# stm32.net
KiCad netlist of a schematic drawn in Altium Designer
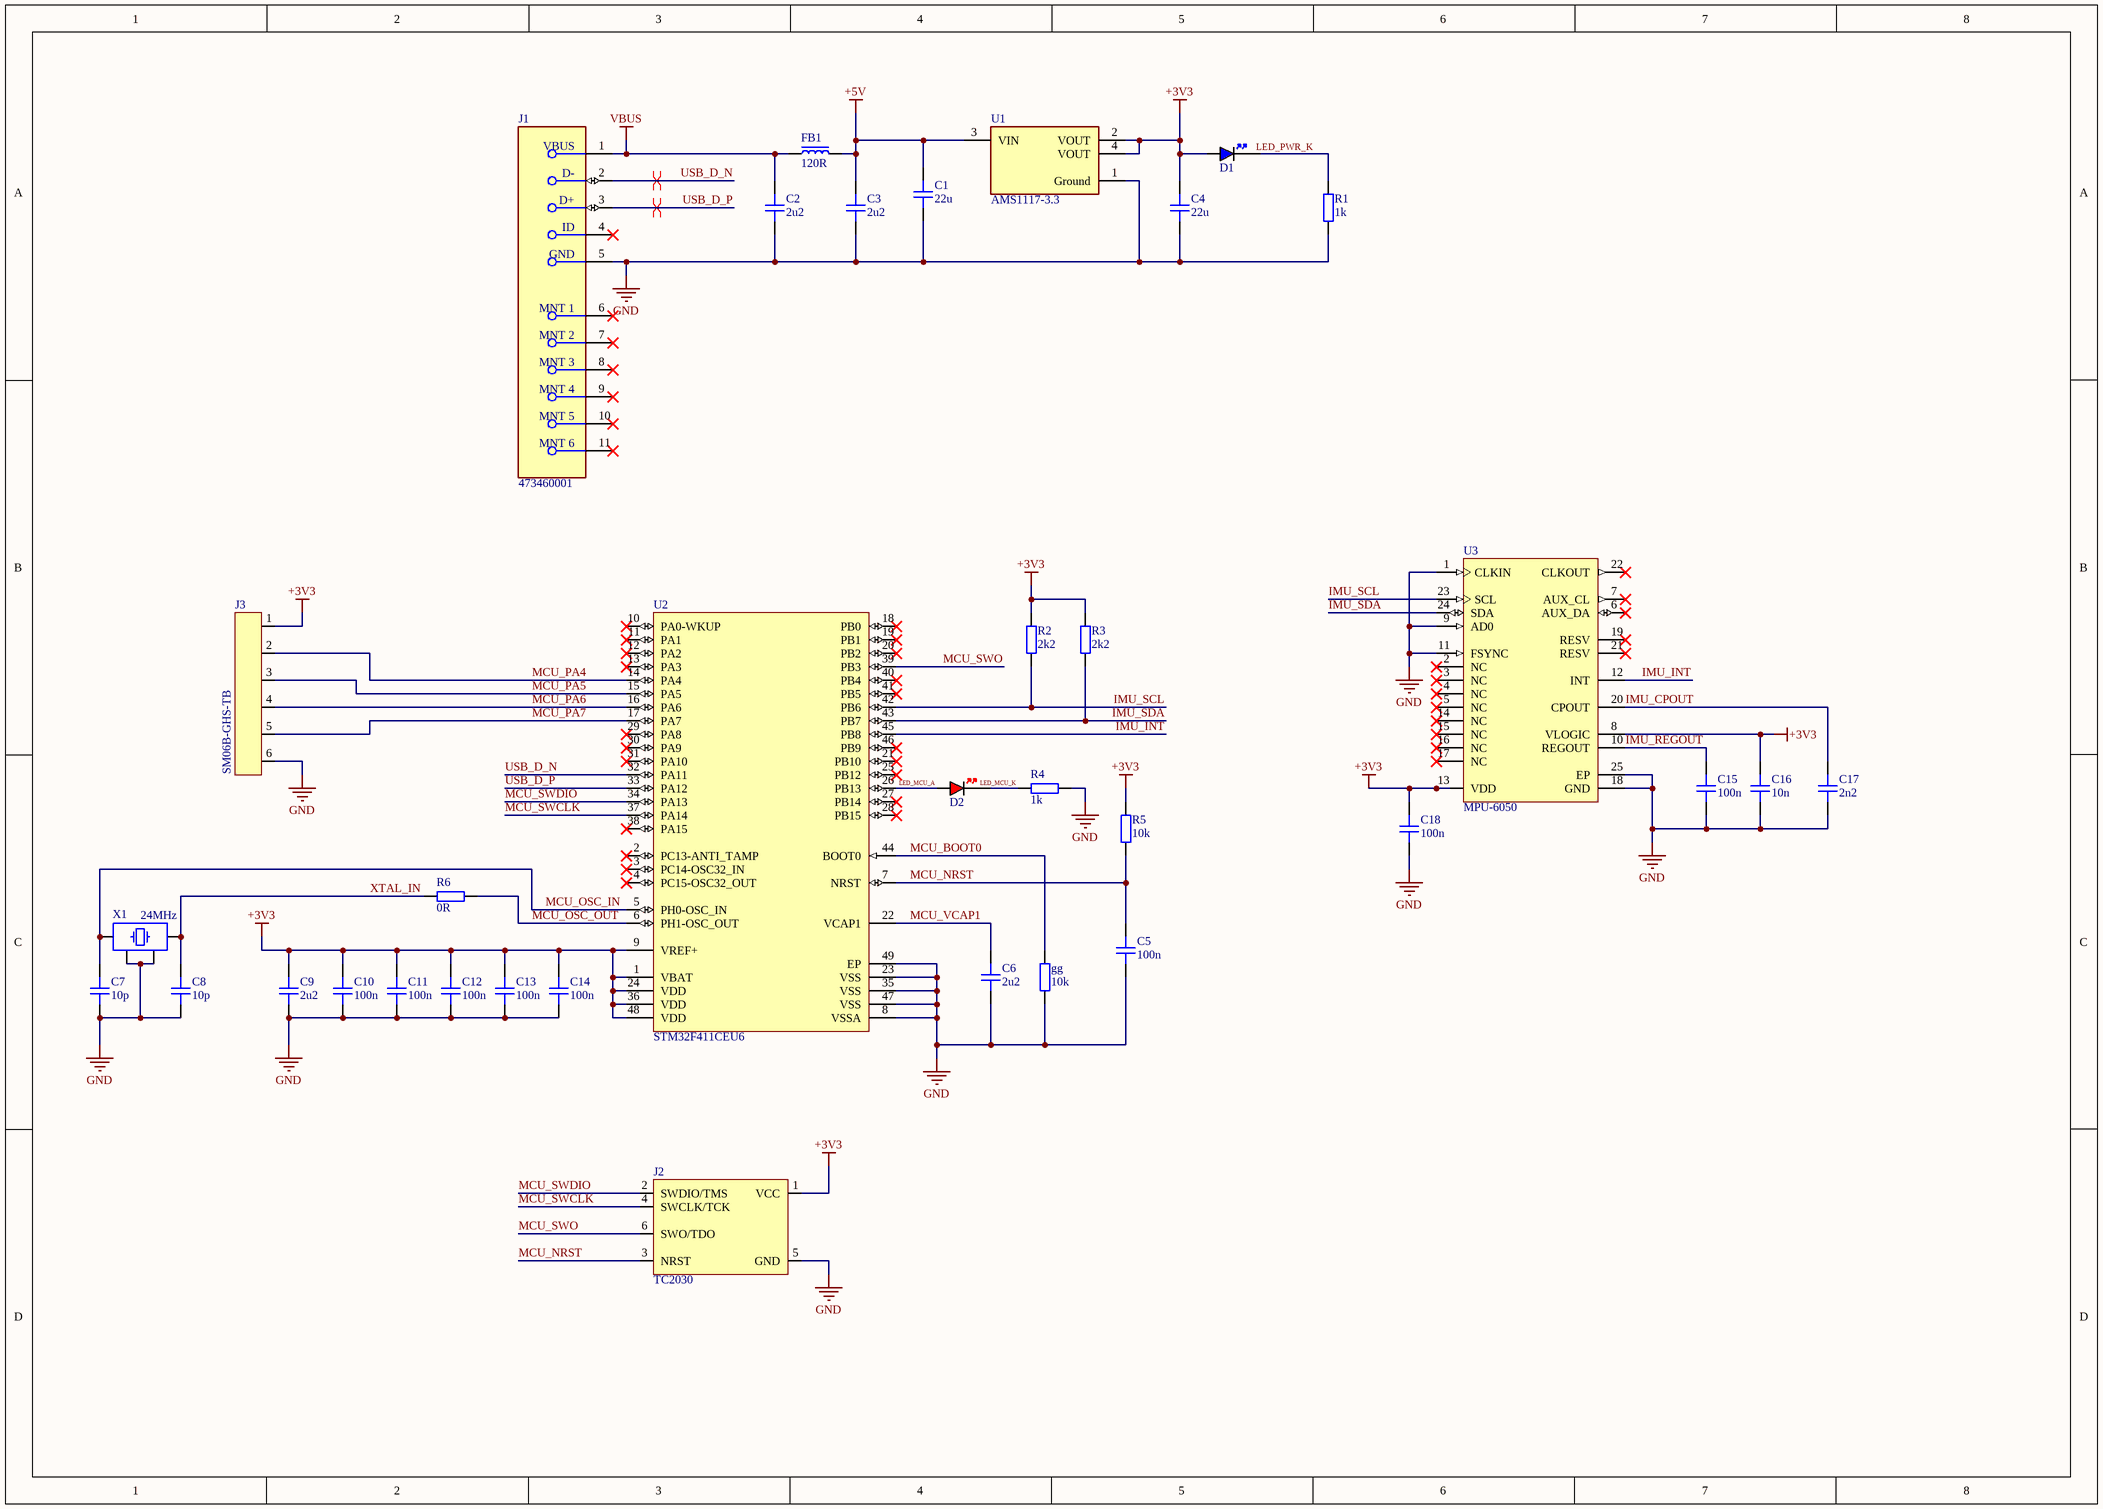
[diagram p0: stm32.SchDoc]

(export (version "E")
  (design (tool "Eeschema 10.0.6"))
  (components
    (comp (ref "C1")
      (value "22u")
      (footprint "CAP_0805")
      (description "Capacitor SMD 0805")
      (libsource (lib "Schematic-Lib-PhilsLab") (part "CAP_0805"))
    )
    (comp (ref "C2")
      (value "2u2")
      (footprint "CAP_0603")
      (description "Capacitor SMD 0603")
      (libsource (lib "Schematic-Lib-PhilsLab") (part "CAP_0603"))
    )
    (comp (ref "C3")
      (value "2u2")
      (footprint "CAP_0603")
      (description "Capacitor SMD 0603")
      (libsource (lib "Schematic-Lib-PhilsLab") (part "CAP_0603"))
    )
    (comp (ref "C4")
      (value "22u")
      (footprint "CAP_0805")
      (description "Capacitor SMD 0805")
      (libsource (lib "Schematic-Lib-PhilsLab") (part "CAP_0805"))
    )
    (comp (ref "C5")
      (value "100n")
      (footprint "CAP_0402")
      (description "Capacitor SMD 0402")
      (libsource (lib "Schematic-Lib-PhilsLab") (part "CAP_0402"))
    )
    (comp (ref "C6")
      (value "2u2")
      (footprint "CAP_0603")
      (description "Capacitor SMD 0603")
      (libsource (lib "Schematic-Lib-PhilsLab") (part "CAP_0603"))
    )
    (comp (ref "C7")
      (value "10p")
      (footprint "CAP_0402")
      (description "Capacitor SMD 0402")
      (libsource (lib "Schematic-Lib-PhilsLab") (part "CAP_0402"))
    )
    (comp (ref "C8")
      (value "10p")
      (footprint "CAP_0402")
      (description "Capacitor SMD 0402")
      (libsource (lib "Schematic-Lib-PhilsLab") (part "CAP_0402"))
    )
    (comp (ref "C9")
      (value "2u2")
      (footprint "CAP_0603")
      (description "Capacitor SMD 0603")
      (libsource (lib "Schematic-Lib-PhilsLab") (part "CAP_0603"))
    )
    (comp (ref "C10")
      (value "100n")
      (footprint "CAP_0402")
      (description "Capacitor SMD 0402")
      (libsource (lib "Schematic-Lib-PhilsLab") (part "CAP_0402"))
    )
    (comp (ref "C11")
      (value "100n")
      (footprint "CAP_0402")
      (description "Capacitor SMD 0402")
      (libsource (lib "Schematic-Lib-PhilsLab") (part "CAP_0402"))
    )
    (comp (ref "C12")
      (value "100n")
      (footprint "CAP_0402")
      (description "Capacitor SMD 0402")
      (libsource (lib "Schematic-Lib-PhilsLab") (part "CAP_0402"))
    )
    (comp (ref "C13")
      (value "100n")
      (footprint "CAP_0402")
      (description "Capacitor SMD 0402")
      (libsource (lib "Schematic-Lib-PhilsLab") (part "CAP_0402"))
    )
    (comp (ref "C14")
      (value "100n")
      (footprint "CAP_0402")
      (description "Capacitor SMD 0402")
      (libsource (lib "Schematic-Lib-PhilsLab") (part "CAP_0402"))
    )
    (comp (ref "C15")
      (value "100n")
      (footprint "CAP_0402")
      (description "Capacitor SMD 0402")
      (libsource (lib "Schematic-Lib-PhilsLab") (part "CAP_0402"))
    )
    (comp (ref "C16")
      (value "10n")
      (footprint "CAP_0402")
      (description "Capacitor SMD 0402")
      (libsource (lib "Schematic-Lib-PhilsLab") (part "CAP_0402"))
    )
    (comp (ref "C17")
      (value "2n2")
      (footprint "CAP_0402")
      (description "Capacitor SMD 0402")
      (libsource (lib "Schematic-Lib-PhilsLab") (part "CAP_0402"))
    )
    (comp (ref "C18")
      (value "100n")
      (footprint "CAP_0402")
      (description "Capacitor SMD 0402")
      (libsource (lib "Schematic-Lib-PhilsLab") (part "CAP_0402"))
    )
    (comp (ref "D1")
      (value "BLUE")
      (footprint "LED_0402_BLUE")
      (description "LED 0402 BLUE SMD")
      (libsource (lib "Schematic-Lib-PhilsLab") (part "LED_0402_BLUE"))
    )
    (comp (ref "D2")
      (value "RED")
      (footprint "LED_0402_RED")
      (description "LED 0402 RED SMD")
      (libsource (lib "Schematic-Lib-PhilsLab") (part "LED_0402_RED"))
    )
    (comp (ref "FB1")
      (value "120R")
      (footprint "FB_0603")
      (description "Ferrite Bead SMD 0603")
      (libsource (lib "Schematic-Lib-PhilsLab") (part "FB_0603"))
    )
    (comp (ref "gg")
      (value "10k")
      (footprint "RES_0402")
      (description "Resistor SMD 0402")
      (libsource (lib "Schematic-Lib-PhilsLab") (part "RES_0402"))
    )
    (comp (ref "J1")
      (value "473460001")
      (footprint "FP-473460001-MFG")
      (description "CONN RCPT USB2.0 MICRO B SMD R/A")
      (fields
        (field (name "OCTOPART") "https://octopart.com/47346-0001-molex-7164928")
        (field (name "MANUFACTURER") "Molex")
      )
      (libsource (lib "Altium Content Vault") (part "53ae1f1d9b557310b43ca686e5bb76a"))
    )
    (comp (ref "J2")
      (value "TC2030")
      (footprint "TC2030-FP")
      (description "Tag-Connect No-Solder SWD Debug Connector DO NOT PLACE")
      (fields (field (name "MANUFACTURER") "Tag-Connect"))
      (libsource (lib "Schematic-Lib-PhilsLab") (part "TC2030"))
    )
    (comp (ref "J3")
      (value "SM06B-GHS-TB")
      (footprint "SM06B-GHS-TB")
      (description "Header Connector 6 Position 1.25MM Pitch SMD Horizontal JST GH")
      (fields (field (name "MANUFACTURER") "JST"))
      (libsource (lib "Schematic-Lib-PhilsLab") (part "SM06B-GHS-TB"))
    )
    (comp (ref "R1")
      (value "1k")
      (footprint "RES_0402")
      (description "Resistor SMD 0402")
      (libsource (lib "Schematic-Lib-PhilsLab") (part "RES_0402"))
    )
    (comp (ref "R2")
      (value "2k2")
      (footprint "RES_0402")
      (description "Resistor SMD 0402")
      (libsource (lib "Schematic-Lib-PhilsLab") (part "RES_0402"))
    )
    (comp (ref "R3")
      (value "2k2")
      (footprint "RES_0402")
      (description "Resistor SMD 0402")
      (libsource (lib "Schematic-Lib-PhilsLab") (part "RES_0402"))
    )
    (comp (ref "R4")
      (value "1k")
      (footprint "RES_0402")
      (description "Resistor SMD 0402")
      (libsource (lib "Schematic-Lib-PhilsLab") (part "RES_0402"))
    )
    (comp (ref "R5")
      (value "10k")
      (footprint "RES_0402")
      (description "Resistor SMD 0402")
      (libsource (lib "Schematic-Lib-PhilsLab") (part "RES_0402"))
    )
    (comp (ref "R6")
      (value "0R")
      (footprint "RES_0402")
      (description "Resistor SMD 0402")
      (libsource (lib "Schematic-Lib-PhilsLab") (part "RES_0402"))
    )
    (comp (ref "U1")
      (value "AMS1117-3.3")
      (footprint "FP-AMS1117-IPC_C")
      (description "LDO Voltage Regulators 1A, 3.3V")
      (fields
        (field (name "OCTOPART") "https://octopart.com/ams1117-3.3-advanced+monolithic+systems-25899300")
        (field (name "MANUFACTURER") "Advanced Monolithic Systems")
      )
      (libsource (lib "Altium Content Vault") (part "8bdbb5f8e77002000e30dd2845d0354"))
    )
    (comp (ref "U2")
      (value "STM32F411CEU6")
      (footprint "STM-UFQFPN48_L")
      (libsource (lib "Altium Content Vault") (part "MC-ARM-STM32F411-UFQFPN48"))
    )
    (comp (ref "U3")
      (value "MPU-6050")
      (footprint "IS-QFN-24_V")
      (fields (field (name "MANUFACTURER") "InvenSense"))
      (libsource (lib "Altium Content Vault") (part "IS-MPU-6050-QFN-24"))
    )
    (comp (ref "X1")
      (value "24MHz")
      (footprint "XTAL_3225")
      (description "Crystal SMD 24MHz 10PPM 7pF 3225")
      (fields
        (field (name "MANUFACTURER") "Epson")
        (field (name "MANUFACTURER PART NUMBER") "TSX-3225 24.0000MF15X-AC")
      )
      (libsource (lib "Schematic-Lib-PhilsLab") (part "TSX-3225_24.0000MF15X-AC"))
    )
  )
  (nets
    (net (code "1") (name "+3V3") (class "Default")
      (node (ref "C10") (pin "2") (pinfunction "2_2") (pintype "passive"))
      (node (ref "C11") (pin "2") (pinfunction "2_2") (pintype "passive"))
      (node (ref "C12") (pin "2") (pinfunction "2_2") (pintype "passive"))
      (node (ref "C13") (pin "2") (pinfunction "2_2") (pintype "passive"))
      (node (ref "C14") (pin "2") (pinfunction "2_2") (pintype "passive"))
      (node (ref "C16") (pin "2") (pinfunction "2_2") (pintype "passive"))
      (node (ref "C18") (pin "2") (pinfunction "2_2") (pintype "passive"))
      (node (ref "C4") (pin "2") (pinfunction "2_2") (pintype "passive"))
      (node (ref "C9") (pin "2") (pinfunction "2_2") (pintype "passive"))
      (node (ref "D1") (pin "A") (pinfunction "A_A") (pintype "passive"))
      (node (ref "J2") (pin "1") (pinfunction "VCC_1") (pintype "passive"))
      (node (ref "J3") (pin "1") (pinfunction "1_1") (pintype "passive"))
      (node (ref "R2") (pin "2") (pinfunction "2_2") (pintype "passive"))
      (node (ref "R3") (pin "2") (pinfunction "2_2") (pintype "passive"))
      (node (ref "R5") (pin "2") (pinfunction "2_2") (pintype "passive"))
      (node (ref "U1") (pin "2") (pinfunction "VOUT_2") (pintype "passive"))
      (node (ref "U1") (pin "4") (pinfunction "VOUT_4") (pintype "passive"))
      (node (ref "U2") (pin "1") (pinfunction "VBAT_1") (pintype "power_in"))
      (node (ref "U2") (pin "24") (pinfunction "VDD_24") (pintype "power_in"))
      (node (ref "U2") (pin "36") (pinfunction "VDD_36") (pintype "power_in"))
      (node (ref "U2") (pin "48") (pinfunction "VDD_48") (pintype "power_in"))
      (node (ref "U2") (pin "9") (pinfunction "VREF+_9") (pintype "power_in"))
      (node (ref "U3") (pin "13") (pinfunction "VDD_13") (pintype "power_in"))
      (node (ref "U3") (pin "8") (pinfunction "VLOGIC_8") (pintype "power_in"))
    )
    (net (code "2") (name "+5V") (class "Default")
      (node (ref "C1") (pin "2") (pinfunction "2_2") (pintype "passive"))
      (node (ref "C3") (pin "2") (pinfunction "2_2") (pintype "passive"))
      (node (ref "FB1") (pin "2") (pinfunction "2_2") (pintype "passive"))
      (node (ref "U1") (pin "3") (pinfunction "VIN_3") (pintype "power_in"))
    )
    (net (code "3") (name "/IMU_CPOUT") (class "Default")
      (node (ref "C17") (pin "2") (pinfunction "2_2") (pintype "passive"))
      (node (ref "U3") (pin "20") (pinfunction "CPOUT_20") (pintype "passive"))
    )
    (net (code "4") (name "/IMU_INT") (class "Default")
      (node (ref "U2") (pin "45") (pinfunction "PB8_45") (pintype "bidirectional"))
      (node (ref "U3") (pin "12") (pinfunction "INT_12") (pintype "open_collector"))
    )
    (net (code "5") (name "/IMU_REGOUT") (class "Default")
      (node (ref "C15") (pin "2") (pinfunction "2_2") (pintype "passive"))
      (node (ref "U3") (pin "10") (pinfunction "REGOUT_10") (pintype "passive"))
    )
    (net (code "6") (name "/IMU_SCL") (class "Default")
      (node (ref "R2") (pin "1") (pinfunction "1_1") (pintype "passive"))
      (node (ref "U2") (pin "42") (pinfunction "PB6_42") (pintype "bidirectional"))
      (node (ref "U3") (pin "23") (pinfunction "SCL_23") (pintype "input"))
    )
    (net (code "7") (name "/IMU_SDA") (class "Default")
      (node (ref "R3") (pin "1") (pinfunction "1_1") (pintype "passive"))
      (node (ref "U2") (pin "43") (pinfunction "PB7_43") (pintype "bidirectional"))
      (node (ref "U3") (pin "24") (pinfunction "SDA_24") (pintype "bidirectional"))
    )
    (net (code "8") (name "/LED_MCU_A") (class "Default")
      (node (ref "D2") (pin "A") (pinfunction "A_A") (pintype "passive"))
      (node (ref "U2") (pin "26") (pinfunction "PB13_26") (pintype "bidirectional"))
    )
    (net (code "9") (name "/LED_MCU_K") (class "Default")
      (node (ref "D2") (pin "K") (pinfunction "K_K") (pintype "passive"))
      (node (ref "R4") (pin "2") (pinfunction "2_2") (pintype "passive"))
    )
    (net (code "10") (name "/LED_PWR_K") (class "Default")
      (node (ref "D1") (pin "K") (pinfunction "K_K") (pintype "passive"))
      (node (ref "R1") (pin "2") (pinfunction "2_2") (pintype "passive"))
    )
    (net (code "11") (name "/MCU_BOOT0") (class "Default")
      (node (ref "U2") (pin "44") (pinfunction "BOOT0_44") (pintype "input"))
      (node (ref "gg") (pin "2") (pinfunction "2_2") (pintype "passive"))
    )
    (net (code "12") (name "/MCU_NRST") (class "Default")
      (node (ref "C5") (pin "2") (pinfunction "2_2") (pintype "passive"))
      (node (ref "J2") (pin "3") (pinfunction "NRST_3") (pintype "passive"))
      (node (ref "R5") (pin "1") (pinfunction "1_1") (pintype "passive"))
      (node (ref "U2") (pin "7") (pinfunction "NRST_7") (pintype "bidirectional"))
    )
    (net (code "13") (name "/MCU_OSC_IN") (class "Default")
      (node (ref "C7") (pin "2") (pinfunction "2_2") (pintype "passive"))
      (node (ref "U2") (pin "5") (pinfunction "PH0-OSC_IN_5") (pintype "bidirectional"))
      (node (ref "X1") (pin "1") (pinfunction "1_1") (pintype "passive"))
    )
    (net (code "14") (name "/MCU_OSC_OUT") (class "Default")
      (node (ref "R6") (pin "1") (pinfunction "1_1") (pintype "passive"))
      (node (ref "U2") (pin "6") (pinfunction "PH1-OSC_OUT_6") (pintype "bidirectional"))
    )
    (net (code "15") (name "/MCU_PA4") (class "Default")
      (node (ref "J3") (pin "2") (pinfunction "2_2") (pintype "passive"))
      (node (ref "U2") (pin "14") (pinfunction "PA4_14") (pintype "bidirectional"))
    )
    (net (code "16") (name "/MCU_PA5") (class "Default")
      (node (ref "J3") (pin "3") (pinfunction "3_3") (pintype "passive"))
      (node (ref "U2") (pin "15") (pinfunction "PA5_15") (pintype "bidirectional"))
    )
    (net (code "17") (name "/MCU_PA6") (class "Default")
      (node (ref "J3") (pin "4") (pinfunction "4_4") (pintype "passive"))
      (node (ref "U2") (pin "16") (pinfunction "PA6_16") (pintype "bidirectional"))
    )
    (net (code "18") (name "/MCU_PA7") (class "Default")
      (node (ref "J3") (pin "5") (pinfunction "5_5") (pintype "passive"))
      (node (ref "U2") (pin "17") (pinfunction "PA7_17") (pintype "bidirectional"))
    )
    (net (code "19") (name "/MCU_SWCLK") (class "Default")
      (node (ref "J2") (pin "4") (pinfunction "SWCLK/TCK_4") (pintype "passive"))
      (node (ref "U2") (pin "37") (pinfunction "PA14_37") (pintype "bidirectional"))
    )
    (net (code "20") (name "/MCU_SWDIO") (class "Default")
      (node (ref "J2") (pin "2") (pinfunction "SWDIO/TMS_2") (pintype "passive"))
      (node (ref "U2") (pin "34") (pinfunction "PA13_34") (pintype "bidirectional"))
    )
    (net (code "21") (name "/MCU_SWO") (class "Default")
      (node (ref "J2") (pin "6") (pinfunction "SWO/TDO_6") (pintype "passive"))
      (node (ref "U2") (pin "39") (pinfunction "PB3_39") (pintype "bidirectional"))
    )
    (net (code "22") (name "/MCU_VCAP1") (class "Default")
      (node (ref "C6") (pin "2") (pinfunction "2_2") (pintype "passive"))
      (node (ref "U2") (pin "22") (pinfunction "VCAP1_22") (pintype "passive"))
    )
    (net (code "23") (name "/USB_D_N") (class "Default")
      (node (ref "J1") (pin "2") (pinfunction "D-_2") (pintype "bidirectional"))
      (node (ref "U2") (pin "32") (pinfunction "PA11_32") (pintype "bidirectional"))
    )
    (net (code "24") (name "/USB_D_P") (class "Default")
      (node (ref "J1") (pin "3") (pinfunction "D+_3") (pintype "bidirectional"))
      (node (ref "U2") (pin "33") (pinfunction "PA12_33") (pintype "bidirectional"))
    )
    (net (code "25") (name "/XTAL_IN") (class "Default")
      (node (ref "C8") (pin "2") (pinfunction "2_2") (pintype "passive"))
      (node (ref "R6") (pin "2") (pinfunction "2_2") (pintype "passive"))
      (node (ref "X1") (pin "3") (pinfunction "3_3") (pintype "passive"))
    )
    (net (code "26") (name "GND") (class "Default")
      (node (ref "C1") (pin "1") (pinfunction "1_1") (pintype "passive"))
      (node (ref "C10") (pin "1") (pinfunction "1_1") (pintype "passive"))
      (node (ref "C11") (pin "1") (pinfunction "1_1") (pintype "passive"))
      (node (ref "C12") (pin "1") (pinfunction "1_1") (pintype "passive"))
      (node (ref "C13") (pin "1") (pinfunction "1_1") (pintype "passive"))
      (node (ref "C14") (pin "1") (pinfunction "1_1") (pintype "passive"))
      (node (ref "C15") (pin "1") (pinfunction "1_1") (pintype "passive"))
      (node (ref "C16") (pin "1") (pinfunction "1_1") (pintype "passive"))
      (node (ref "C17") (pin "1") (pinfunction "1_1") (pintype "passive"))
      (node (ref "C18") (pin "1") (pinfunction "1_1") (pintype "passive"))
      (node (ref "C2") (pin "1") (pinfunction "1_1") (pintype "passive"))
      (node (ref "C3") (pin "1") (pinfunction "1_1") (pintype "passive"))
      (node (ref "C4") (pin "1") (pinfunction "1_1") (pintype "passive"))
      (node (ref "C5") (pin "1") (pinfunction "1_1") (pintype "passive"))
      (node (ref "C6") (pin "1") (pinfunction "1_1") (pintype "passive"))
      (node (ref "C7") (pin "1") (pinfunction "1_1") (pintype "passive"))
      (node (ref "C8") (pin "1") (pinfunction "1_1") (pintype "passive"))
      (node (ref "C9") (pin "1") (pinfunction "1_1") (pintype "passive"))
      (node (ref "J1") (pin "5") (pinfunction "GND_5") (pintype "power_in"))
      (node (ref "J2") (pin "5") (pinfunction "GND_5") (pintype "passive"))
      (node (ref "J3") (pin "6") (pinfunction "6_6") (pintype "passive"))
      (node (ref "R1") (pin "1") (pinfunction "1_1") (pintype "passive"))
      (node (ref "R4") (pin "1") (pinfunction "1_1") (pintype "passive"))
      (node (ref "U1") (pin "1") (pinfunction "Ground_1") (pintype "power_in"))
      (node (ref "U2") (pin "23") (pinfunction "VSS_23") (pintype "power_in"))
      (node (ref "U2") (pin "35") (pinfunction "VSS_35") (pintype "power_in"))
      (node (ref "U2") (pin "47") (pinfunction "VSS_47") (pintype "power_in"))
      (node (ref "U2") (pin "49") (pinfunction "EP_49") (pintype "power_in"))
      (node (ref "U2") (pin "8") (pinfunction "VSSA_8") (pintype "power_in"))
      (node (ref "U3") (pin "1") (pinfunction "CLKIN_1") (pintype "input"))
      (node (ref "U3") (pin "11") (pinfunction "FSYNC_11") (pintype "input"))
      (node (ref "U3") (pin "18") (pinfunction "GND_18") (pintype "power_in"))
      (node (ref "U3") (pin "25") (pinfunction "EP_25") (pintype "power_in"))
      (node (ref "U3") (pin "9") (pinfunction "AD0_9") (pintype "input"))
      (node (ref "X1") (pin "2") (pinfunction "2_2") (pintype "passive"))
      (node (ref "X1") (pin "4") (pinfunction "4_4") (pintype "passive"))
      (node (ref "gg") (pin "1") (pinfunction "1_1") (pintype "passive"))
    )
    (net (code "27") (name "VBUS") (class "Default")
      (node (ref "C2") (pin "2") (pinfunction "2_2") (pintype "passive"))
      (node (ref "FB1") (pin "1") (pinfunction "1_1") (pintype "passive"))
      (node (ref "J1") (pin "1") (pinfunction "VBUS_1") (pintype "power_in"))
    )
    (net (code "28") (name "unconnected-(J1-ID-Pad4)") (class "Default")
      (node (ref "J1") (pin "4") (pinfunction "ID_4") (pintype "passive+no_connect"))
    )
    (net (code "29") (name "unconnected-(J1-MNT_1-Pad6)") (class "Default")
      (node (ref "J1") (pin "6") (pinfunction "MNT_1_6") (pintype "passive+no_connect"))
    )
    (net (code "30") (name "unconnected-(J1-MNT_2-Pad7)") (class "Default")
      (node (ref "J1") (pin "7") (pinfunction "MNT_2_7") (pintype "passive+no_connect"))
    )
    (net (code "31") (name "unconnected-(J1-MNT_3-Pad8)") (class "Default")
      (node (ref "J1") (pin "8") (pinfunction "MNT_3_8") (pintype "passive+no_connect"))
    )
    (net (code "32") (name "unconnected-(J1-MNT_4-Pad9)") (class "Default")
      (node (ref "J1") (pin "9") (pinfunction "MNT_4_9") (pintype "passive+no_connect"))
    )
    (net (code "33") (name "unconnected-(J1-MNT_5-Pad10)") (class "Default")
      (node (ref "J1") (pin "10") (pinfunction "MNT_5_10") (pintype "passive+no_connect"))
    )
    (net (code "34") (name "unconnected-(J1-MNT_6-Pad11)") (class "Default")
      (node (ref "J1") (pin "11") (pinfunction "MNT_6_11") (pintype "passive+no_connect"))
    )
    (net (code "35") (name "unconnected-(U2-PA0-WKUP-Pad10)") (class "Default")
      (node (ref "U2") (pin "10") (pinfunction "PA0-WKUP_10") (pintype "bidirectional+no_connect"))
    )
    (net (code "36") (name "unconnected-(U2-PA1-Pad11)") (class "Default")
      (node (ref "U2") (pin "11") (pinfunction "PA1_11") (pintype "bidirectional+no_connect"))
    )
    (net (code "37") (name "unconnected-(U2-PA2-Pad12)") (class "Default")
      (node (ref "U2") (pin "12") (pinfunction "PA2_12") (pintype "bidirectional+no_connect"))
    )
    (net (code "38") (name "unconnected-(U2-PA3-Pad13)") (class "Default")
      (node (ref "U2") (pin "13") (pinfunction "PA3_13") (pintype "bidirectional+no_connect"))
    )
    (net (code "39") (name "unconnected-(U2-PA8-Pad29)") (class "Default")
      (node (ref "U2") (pin "29") (pinfunction "PA8_29") (pintype "bidirectional+no_connect"))
    )
    (net (code "40") (name "unconnected-(U2-PA9-Pad30)") (class "Default")
      (node (ref "U2") (pin "30") (pinfunction "PA9_30") (pintype "bidirectional+no_connect"))
    )
    (net (code "41") (name "unconnected-(U2-PA10-Pad31)") (class "Default")
      (node (ref "U2") (pin "31") (pinfunction "PA10_31") (pintype "bidirectional+no_connect"))
    )
    (net (code "42") (name "unconnected-(U2-PA15-Pad38)") (class "Default")
      (node (ref "U2") (pin "38") (pinfunction "PA15_38") (pintype "bidirectional+no_connect"))
    )
    (net (code "43") (name "unconnected-(U2-PB0-Pad18)") (class "Default")
      (node (ref "U2") (pin "18") (pinfunction "PB0_18") (pintype "bidirectional+no_connect"))
    )
    (net (code "44") (name "unconnected-(U2-PB1-Pad19)") (class "Default")
      (node (ref "U2") (pin "19") (pinfunction "PB1_19") (pintype "bidirectional+no_connect"))
    )
    (net (code "45") (name "unconnected-(U2-PB2-Pad20)") (class "Default")
      (node (ref "U2") (pin "20") (pinfunction "PB2_20") (pintype "bidirectional+no_connect"))
    )
    (net (code "46") (name "unconnected-(U2-PB4-Pad40)") (class "Default")
      (node (ref "U2") (pin "40") (pinfunction "PB4_40") (pintype "bidirectional+no_connect"))
    )
    (net (code "47") (name "unconnected-(U2-PB5-Pad41)") (class "Default")
      (node (ref "U2") (pin "41") (pinfunction "PB5_41") (pintype "bidirectional+no_connect"))
    )
    (net (code "48") (name "unconnected-(U2-PB9-Pad46)") (class "Default")
      (node (ref "U2") (pin "46") (pinfunction "PB9_46") (pintype "bidirectional+no_connect"))
    )
    (net (code "49") (name "unconnected-(U2-PB10-Pad21)") (class "Default")
      (node (ref "U2") (pin "21") (pinfunction "PB10_21") (pintype "bidirectional+no_connect"))
    )
    (net (code "50") (name "unconnected-(U2-PB12-Pad25)") (class "Default")
      (node (ref "U2") (pin "25") (pinfunction "PB12_25") (pintype "bidirectional+no_connect"))
    )
    (net (code "51") (name "unconnected-(U2-PB14-Pad27)") (class "Default")
      (node (ref "U2") (pin "27") (pinfunction "PB14_27") (pintype "bidirectional+no_connect"))
    )
    (net (code "52") (name "unconnected-(U2-PB15-Pad28)") (class "Default")
      (node (ref "U2") (pin "28") (pinfunction "PB15_28") (pintype "bidirectional+no_connect"))
    )
    (net (code "53") (name "unconnected-(U2-PC13-ANTI_TAMP-Pad2)") (class "Default")
      (node (ref "U2") (pin "2") (pinfunction "PC13-ANTI_TAMP_2") (pintype "bidirectional+no_connect"))
    )
    (net (code "54") (name "unconnected-(U2-PC14-OSC32_IN-Pad3)") (class "Default")
      (node (ref "U2") (pin "3") (pinfunction "PC14-OSC32_IN_3") (pintype "bidirectional+no_connect"))
    )
    (net (code "55") (name "unconnected-(U2-PC15-OSC32_OUT-Pad4)") (class "Default")
      (node (ref "U2") (pin "4") (pinfunction "PC15-OSC32_OUT_4") (pintype "bidirectional+no_connect"))
    )
    (net (code "56") (name "unconnected-(U3-AUX_CL-Pad7)") (class "Default")
      (node (ref "U3") (pin "7") (pinfunction "AUX_CL_7") (pintype "output+no_connect"))
    )
    (net (code "57") (name "unconnected-(U3-AUX_DA-Pad6)") (class "Default")
      (node (ref "U3") (pin "6") (pinfunction "AUX_DA_6") (pintype "bidirectional+no_connect"))
    )
    (net (code "58") (name "unconnected-(U3-CLKOUT-Pad22)") (class "Default")
      (node (ref "U3") (pin "22") (pinfunction "CLKOUT_22") (pintype "output+no_connect"))
    )
    (net (code "59") (name "unconnected-(U3-NC-Pad2)") (class "Default")
      (node (ref "U3") (pin "2") (pinfunction "NC_2") (pintype "passive+no_connect"))
    )
    (net (code "60") (name "unconnected-(U3-NC-Pad3)") (class "Default")
      (node (ref "U3") (pin "3") (pinfunction "NC_3") (pintype "passive+no_connect"))
    )
    (net (code "61") (name "unconnected-(U3-NC-Pad4)") (class "Default")
      (node (ref "U3") (pin "4") (pinfunction "NC_4") (pintype "passive+no_connect"))
    )
    (net (code "62") (name "unconnected-(U3-NC-Pad5)") (class "Default")
      (node (ref "U3") (pin "5") (pinfunction "NC_5") (pintype "passive+no_connect"))
    )
    (net (code "63") (name "unconnected-(U3-NC-Pad14)") (class "Default")
      (node (ref "U3") (pin "14") (pinfunction "NC_14") (pintype "passive+no_connect"))
    )
    (net (code "64") (name "unconnected-(U3-NC-Pad15)") (class "Default")
      (node (ref "U3") (pin "15") (pinfunction "NC_15") (pintype "passive+no_connect"))
    )
    (net (code "65") (name "unconnected-(U3-NC-Pad16)") (class "Default")
      (node (ref "U3") (pin "16") (pinfunction "NC_16") (pintype "passive+no_connect"))
    )
    (net (code "66") (name "unconnected-(U3-NC-Pad17)") (class "Default")
      (node (ref "U3") (pin "17") (pinfunction "NC_17") (pintype "passive+no_connect"))
    )
    (net (code "67") (name "unconnected-(U3-RESV-Pad19)") (class "Default")
      (node (ref "U3") (pin "19") (pinfunction "RESV_19") (pintype "passive+no_connect"))
    )
    (net (code "68") (name "unconnected-(U3-RESV-Pad21)") (class "Default")
      (node (ref "U3") (pin "21") (pinfunction "RESV_21") (pintype "passive+no_connect"))
    )
  )
)
